# 18V_to_26V_Boost_v3_National.net
KiCad netlist of a schematic drawn in EAGLE
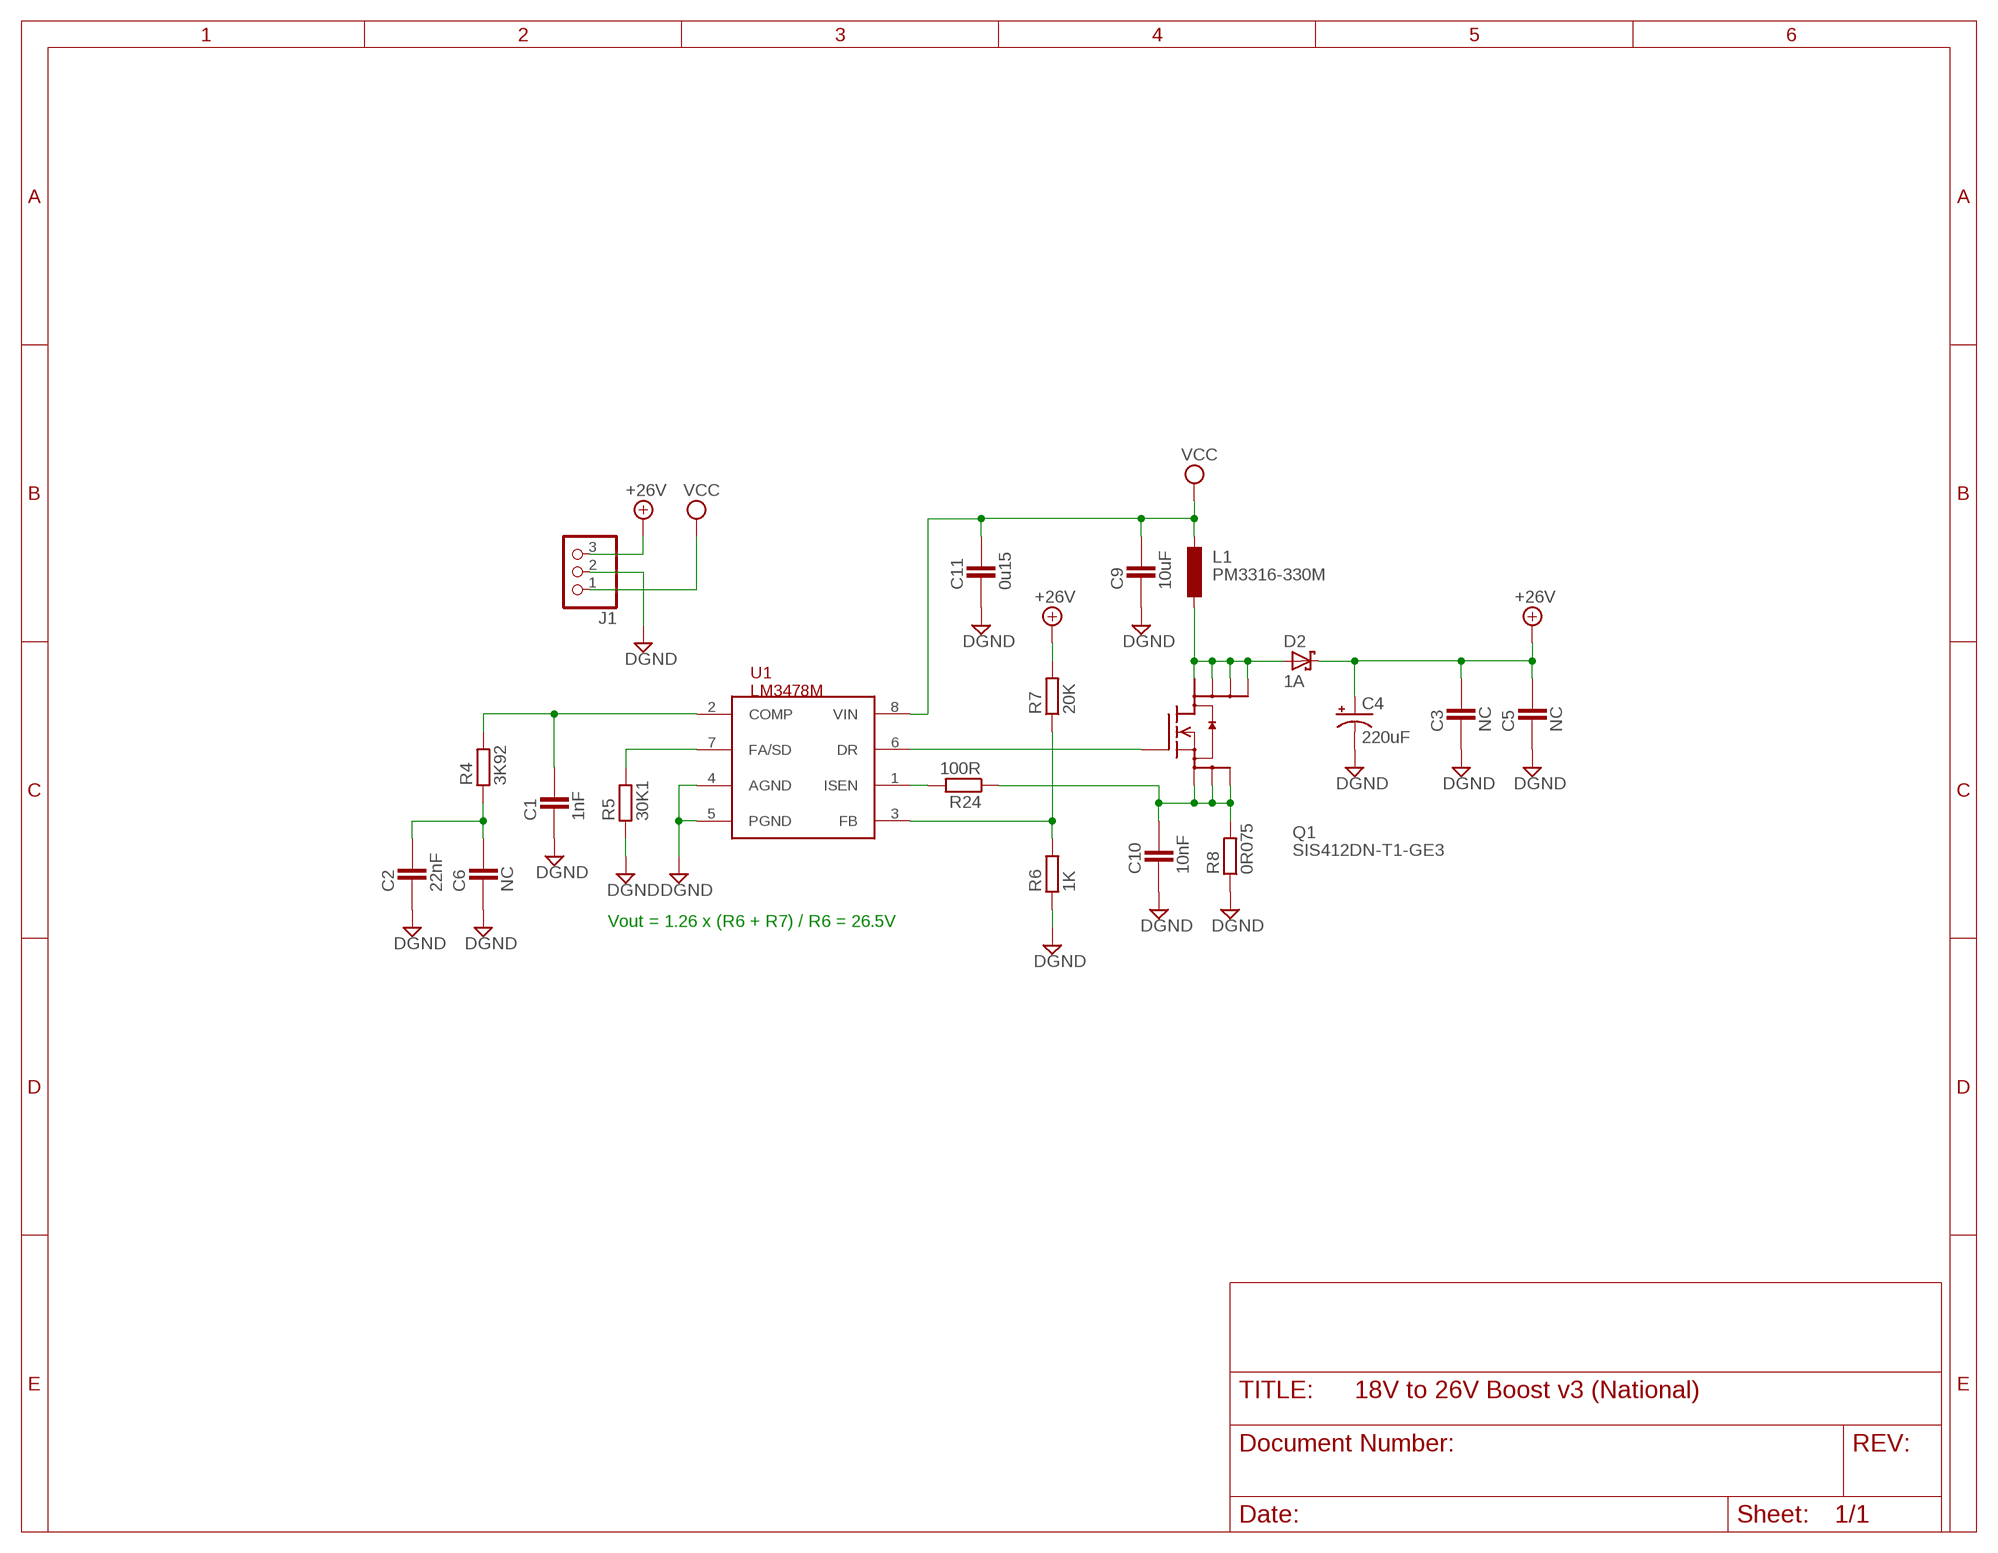
[diagram p0: schematic, sheet 1]

(export (version "E")
  (design (tool "Eeschema 10.0.6"))
  (components
    (comp (ref "C1")
      (value "1nF")
      (footprint "eagle-import:CAP2012X70N")
      (libsource (lib "eagle-import") (part "CAPACITOR_0805N"))
    )
    (comp (ref "C2")
      (value "22nF")
      (footprint "eagle-import:CAPC1608X92N")
      (libsource (lib "eagle-import") (part "CAPACITOR_0603"))
    )
    (comp (ref "C3")
      (value "NC")
      (footprint "eagle-import:CAPC3225X168N")
      (libsource (lib "eagle-import") (part "CAPACITOR_1210"))
    )
    (comp (ref "C4")
      (value "220uF")
      (footprint "eagle-import:PANASONIC_G")
      (libsource (lib "eagle-import") (part "CAP_POLG"))
    )
    (comp (ref "C5")
      (value "NC")
      (footprint "eagle-import:CAPC3225X168N")
      (libsource (lib "eagle-import") (part "CAPACITOR_1210"))
    )
    (comp (ref "C6")
      (value "NC")
      (footprint "eagle-import:CAPC1608X92N")
      (libsource (lib "eagle-import") (part "CAPACITOR_0603"))
    )
    (comp (ref "C9")
      (value "10uF")
      (footprint "eagle-import:CAPC3225X168N")
      (libsource (lib "eagle-import") (part "CAPACITOR_1210"))
    )
    (comp (ref "C10")
      (value "10nF")
      (footprint "eagle-import:CAPC1608X92N")
      (libsource (lib "eagle-import") (part "CAPACITOR_0603"))
    )
    (comp (ref "C11")
      (value "0u15")
      (footprint "eagle-import:CAP2012X70N")
      (libsource (lib "eagle-import") (part "CAPACITOR_0805N"))
    )
    (comp (ref "D2")
      (value "1A")
      (footprint "eagle-import:DIOM5436X265N")
      (libsource (lib "eagle-import") (part "SCHOTTKY_SMB"))
    )
    (comp (ref "J1")
      (value "PINHD-1X3")
      (footprint "eagle-import:1X03")
      (libsource (lib "eagle-import") (part "PINHD-1X3"))
    )
    (comp (ref "L1")
      (value "PM3316-330M")
      (footprint "eagle-import:DO3316P")
      (libsource (lib "eagle-import") (part "DO3316P"))
    )
    (comp (ref "Q1")
      (value "SIS412DN-T1-GE3")
      (footprint "eagle-import:POWER-PAK1212")
      (libsource (lib "eagle-import") (part "MOSFET-NCH_8_1212"))
    )
    (comp (ref "R4")
      (value "3K92")
      (footprint "eagle-import:RESC1608X55N")
      (libsource (lib "eagle-import") (part "RESISTOR_0603"))
    )
    (comp (ref "R5")
      (value "30K1")
      (footprint "eagle-import:RESC1608X55N")
      (libsource (lib "eagle-import") (part "RESISTOR_0603"))
    )
    (comp (ref "R6")
      (value "1K")
      (footprint "eagle-import:RESC1608X55N")
      (libsource (lib "eagle-import") (part "RESISTOR_0603"))
    )
    (comp (ref "R7")
      (value "20K")
      (footprint "eagle-import:RESC1608X55N")
      (libsource (lib "eagle-import") (part "RESISTOR_0603"))
    )
    (comp (ref "R8")
      (value "0R075")
      (footprint "eagle-import:RESC6432X70N")
      (libsource (lib "eagle-import") (part "RESISTOR_2512"))
    )
    (comp (ref "R24")
      (value "100R")
      (footprint "eagle-import:RESC1608X55N")
      (libsource (lib "eagle-import") (part "RESISTOR_0603"))
    )
    (comp (ref "U1")
      (value "LM3478M")
      (footprint "eagle-import:MSOP08")
      (libsource (lib "eagle-import") (part "LM3478M"))
    )
  )
  (nets
    (net (code "1") (name "+26V") (class "Default")
      (node (ref "C3") (pin "2") (pinfunction "2_2") (pintype "passive"))
      (node (ref "C4") (pin "+") (pinfunction "+_+") (pintype "passive"))
      (node (ref "C5") (pin "2") (pinfunction "2_2") (pintype "passive"))
      (node (ref "D2") (pin "K") (pinfunction "K_K") (pintype "passive"))
      (node (ref "J1") (pin "3") (pinfunction "3_3") (pintype "passive"))
      (node (ref "R7") (pin "2") (pinfunction "2_2") (pintype "passive"))
    )
    (net (code "2") (name "DGND") (class "Default")
      (node (ref "C1") (pin "1") (pinfunction "1_1") (pintype "passive"))
      (node (ref "C10") (pin "1") (pinfunction "1_1") (pintype "passive"))
      (node (ref "C11") (pin "1") (pinfunction "1_1") (pintype "passive"))
      (node (ref "C2") (pin "1") (pinfunction "1_1") (pintype "passive"))
      (node (ref "C3") (pin "1") (pinfunction "1_1") (pintype "passive"))
      (node (ref "C4") (pin "-") (pinfunction "-_-") (pintype "passive"))
      (node (ref "C5") (pin "1") (pinfunction "1_1") (pintype "passive"))
      (node (ref "C6") (pin "1") (pinfunction "1_1") (pintype "passive"))
      (node (ref "C9") (pin "1") (pinfunction "1_1") (pintype "passive"))
      (node (ref "J1") (pin "2") (pinfunction "2_2") (pintype "passive"))
      (node (ref "R5") (pin "1") (pinfunction "1_1") (pintype "passive"))
      (node (ref "R6") (pin "1") (pinfunction "1_1") (pintype "passive"))
      (node (ref "R8") (pin "1") (pinfunction "1_1") (pintype "passive"))
      (node (ref "U1") (pin "4") (pinfunction "AGND_4") (pintype "bidirectional"))
      (node (ref "U1") (pin "5") (pinfunction "PGND_5") (pintype "bidirectional"))
    )
    (net (code "3") (name "Net-(C2-Pad2)") (class "Default")
      (node (ref "C2") (pin "2") (pinfunction "2_2") (pintype "passive"))
      (node (ref "C6") (pin "2") (pinfunction "2_2") (pintype "passive"))
      (node (ref "R4") (pin "1") (pinfunction "1_1") (pintype "passive"))
    )
    (net (code "4") (name "Net-(Q1-D1)") (class "Default")
      (node (ref "D2") (pin "A") (pinfunction "A_A") (pintype "passive"))
      (node (ref "L1") (pin "2") (pinfunction "2_2") (pintype "passive"))
      (node (ref "Q1") (pin "5") (pinfunction "D1_5") (pintype "passive"))
      (node (ref "Q1") (pin "6") (pinfunction "D2_6") (pintype "passive"))
      (node (ref "Q1") (pin "7") (pinfunction "D3_7") (pintype "passive"))
      (node (ref "Q1") (pin "8") (pinfunction "D4_8") (pintype "passive"))
    )
    (net (code "5") (name "Net-(Q1-G)") (class "Default")
      (node (ref "Q1") (pin "4") (pinfunction "G_4") (pintype "passive"))
      (node (ref "U1") (pin "6") (pinfunction "DR_6") (pintype "bidirectional"))
    )
    (net (code "6") (name "Net-(Q1-S1)") (class "Default")
      (node (ref "C10") (pin "2") (pinfunction "2_2") (pintype "passive"))
      (node (ref "Q1") (pin "1") (pinfunction "S1_1") (pintype "passive"))
      (node (ref "Q1") (pin "2") (pinfunction "S2_2") (pintype "passive"))
      (node (ref "Q1") (pin "3") (pinfunction "S3_3") (pintype "passive"))
      (node (ref "R24") (pin "1") (pinfunction "1_1") (pintype "passive"))
      (node (ref "R8") (pin "2") (pinfunction "2_2") (pintype "passive"))
    )
    (net (code "7") (name "Net-(U1-COMP)") (class "Default")
      (node (ref "C1") (pin "2") (pinfunction "2_2") (pintype "passive"))
      (node (ref "R4") (pin "2") (pinfunction "2_2") (pintype "passive"))
      (node (ref "U1") (pin "2") (pinfunction "COMP_2") (pintype "bidirectional"))
    )
    (net (code "8") (name "Net-(U1-FA{slash}SD)") (class "Default")
      (node (ref "R5") (pin "2") (pinfunction "2_2") (pintype "passive"))
      (node (ref "U1") (pin "7") (pinfunction "FA/SD_7") (pintype "bidirectional"))
    )
    (net (code "9") (name "Net-(U1-FB)") (class "Default")
      (node (ref "R6") (pin "2") (pinfunction "2_2") (pintype "passive"))
      (node (ref "R7") (pin "1") (pinfunction "1_1") (pintype "passive"))
      (node (ref "U1") (pin "3") (pinfunction "FB_3") (pintype "bidirectional"))
    )
    (net (code "10") (name "Net-(U1-ISEN)") (class "Default")
      (node (ref "R24") (pin "2") (pinfunction "2_2") (pintype "passive"))
      (node (ref "U1") (pin "1") (pinfunction "ISEN_1") (pintype "bidirectional"))
    )
    (net (code "11") (name "VCC") (class "Default")
      (node (ref "C11") (pin "2") (pinfunction "2_2") (pintype "passive"))
      (node (ref "C9") (pin "2") (pinfunction "2_2") (pintype "passive"))
      (node (ref "J1") (pin "1") (pinfunction "1_1") (pintype "passive"))
      (node (ref "L1") (pin "1") (pinfunction "1_1") (pintype "passive"))
      (node (ref "U1") (pin "8") (pinfunction "VIN_8") (pintype "bidirectional"))
    )
  )
)
